# IRRemote.net
KiCad netlist of a schematic drawn in EAGLE
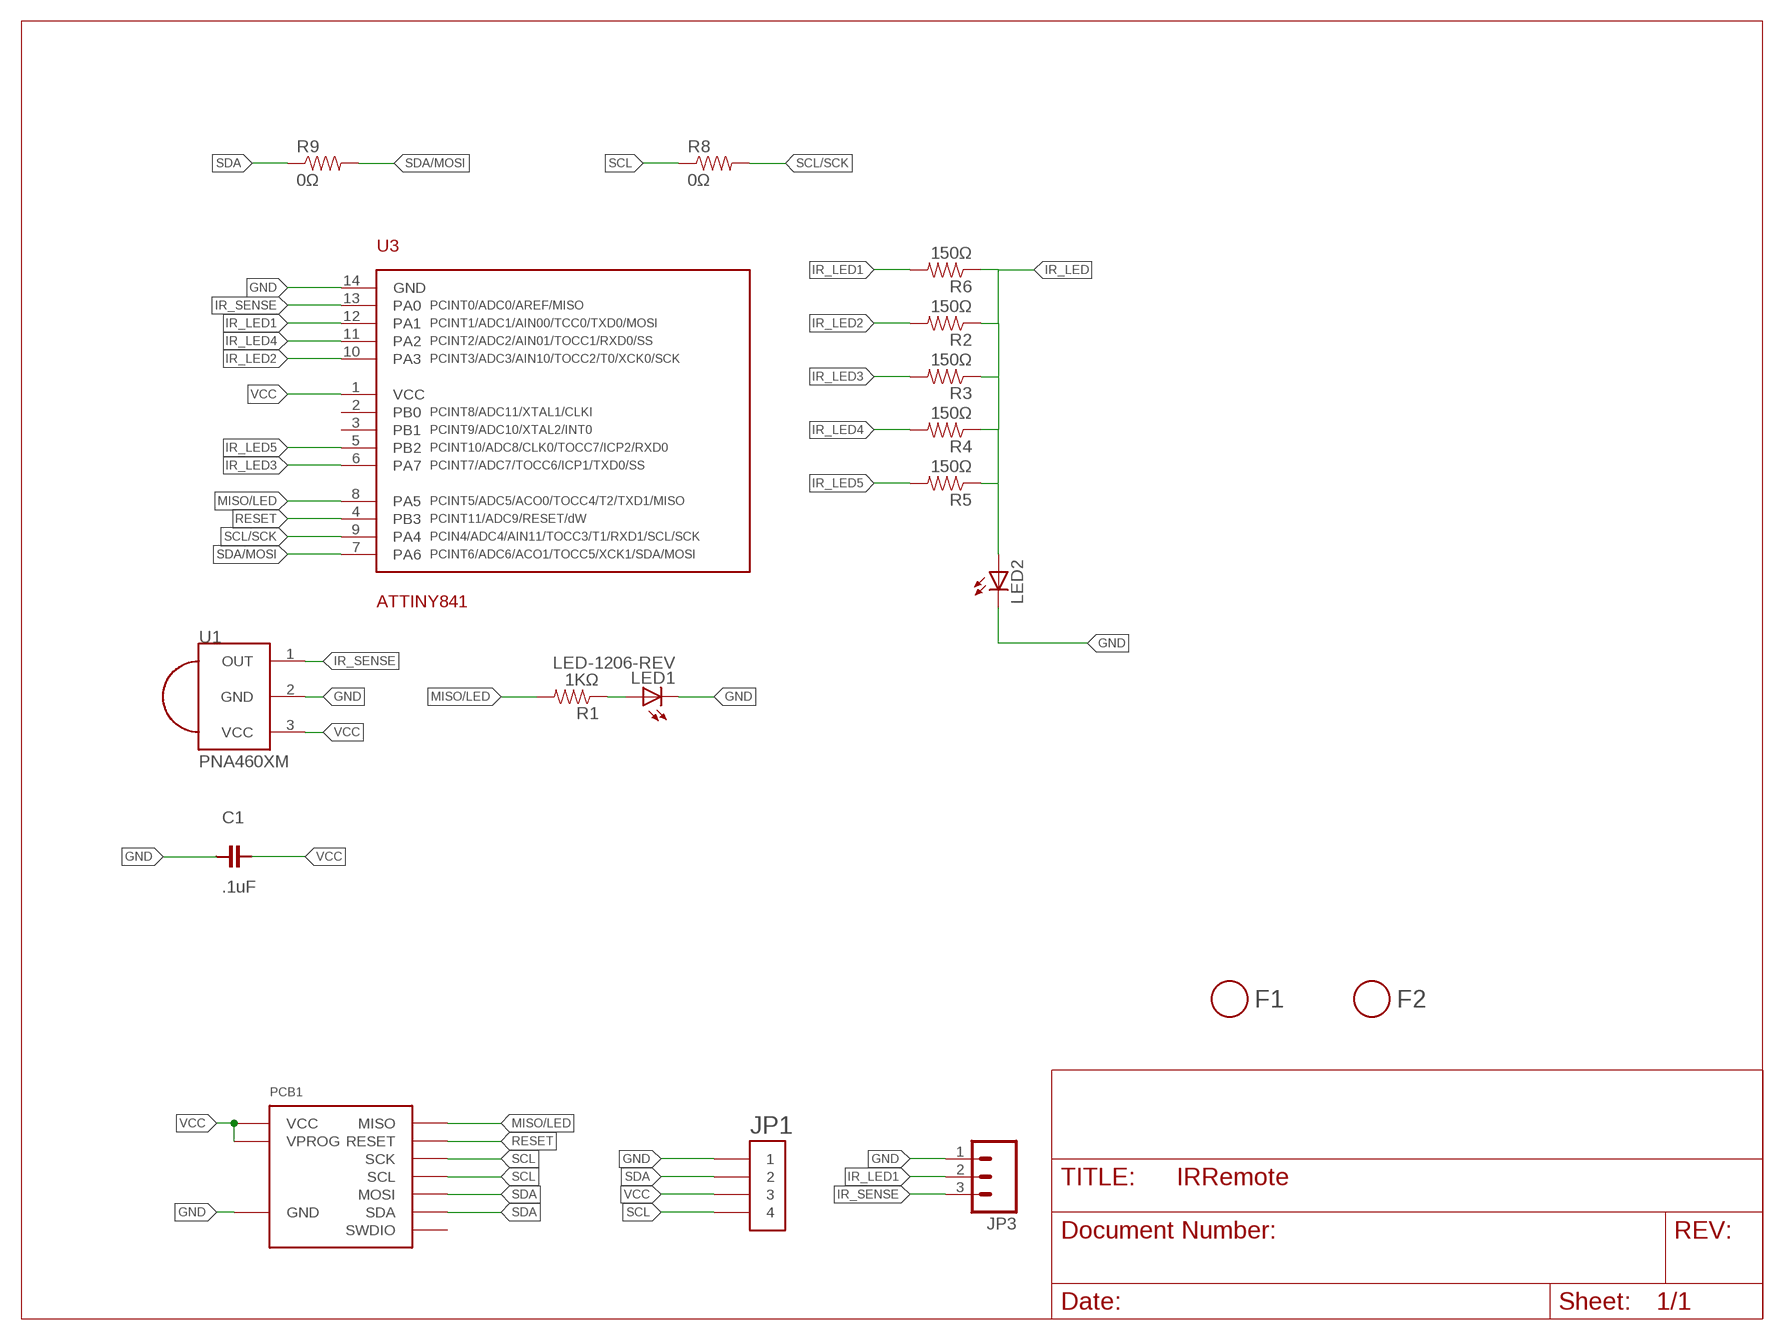
[diagram p0: schematic, sheet 1]

(export (version "E")
  (design (tool "Eeschema 10.0.6"))
  (components
    (comp (ref "C1")
      (value ".1uF")
      (footprint "eagle-import:0603")
      (fields (field (name "PARTNUM") "C0603C104K5RACTU"))
      (libsource (lib "eagle-import") (part "CAPACITOR-.1UF"))
    )
    (comp (ref "F1")
      (value "FIDUCIAL")
      (footprint "eagle-import:FIDUCIAL_1MM")
      (libsource (lib "eagle-import") (part "FIDUCIAL"))
    )
    (comp (ref "F2")
      (value "FIDUCIAL")
      (footprint "eagle-import:FIDUCIAL_1MM")
      (libsource (lib "eagle-import") (part "FIDUCIAL"))
    )
    (comp (ref "JP1")
      (value "HEADER-1X4-AMPMODU")
      (footprint "eagle-import:AMPMODU-4P")
      (fields (field (name "PARTNUM") "147721-3"))
      (libsource (lib "eagle-import") (part "HEADER-1X4-AMPMODU"))
    )
    (comp (ref "JP3")
      (value "M03PTH")
      (footprint "eagle-import:1X03")
      (libsource (lib "eagle-import") (part "M03PTH"))
    )
    (comp (ref "LED1")
      (value "LED-1206-REV")
      (footprint "eagle-import:LED-1206-REV")
      (fields (field (name "PARTNUM") "LTST-C230TBKT"))
      (libsource (lib "eagle-import") (part "LED-1206-REV"))
    )
    (comp (ref "LED2")
      (value "LED5MM")
      (footprint "eagle-import:LED5MM")
      (fields (field (name "PARTNUM") "IR928-6C-F"))
      (libsource (lib "eagle-import") (part "LED5MM"))
    )
    (comp (ref "PCB1")
      (value "DEVICE-PCB")
      (footprint "eagle-import:DEVICE-PCB")
      (fields (field (name "PARTNUM") "IRRemote PCB"))
      (libsource (lib "eagle-import") (part "DEVICE-PCB"))
    )
    (comp (ref "R1")
      (value "1KΩ")
      (footprint "eagle-import:0603")
      (fields (field (name "PARTNUM") "ERJ-3EKF1001V"))
      (libsource (lib "eagle-import") (part "RESISTOR-1KΩ"))
    )
    (comp (ref "R2")
      (value "150Ω")
      (footprint "eagle-import:0603")
      (fields (field (name "PARTNUM") "ERJ-3EKF1500V"))
      (libsource (lib "eagle-import") (part "RESISTOR-150Ω"))
    )
    (comp (ref "R3")
      (value "150Ω")
      (footprint "eagle-import:0603")
      (fields (field (name "PARTNUM") "ERJ-3EKF1500V"))
      (libsource (lib "eagle-import") (part "RESISTOR-150Ω"))
    )
    (comp (ref "R4")
      (value "150Ω")
      (footprint "eagle-import:0603")
      (fields (field (name "PARTNUM") "ERJ-3EKF1500V"))
      (libsource (lib "eagle-import") (part "RESISTOR-150Ω"))
    )
    (comp (ref "R5")
      (value "150Ω")
      (footprint "eagle-import:0603")
      (fields (field (name "PARTNUM") "ERJ-3EKF1500V"))
      (libsource (lib "eagle-import") (part "RESISTOR-150Ω"))
    )
    (comp (ref "R6")
      (value "150Ω")
      (footprint "eagle-import:0603")
      (fields (field (name "PARTNUM") "ERJ-3EKF1500V"))
      (libsource (lib "eagle-import") (part "RESISTOR-150Ω"))
    )
    (comp (ref "R8")
      (value "0Ω")
      (footprint "eagle-import:0603")
      (fields (field (name "PARTNUM") "ERJ-3GEY0R00V"))
      (libsource (lib "eagle-import") (part "RESISTOR-0Ω"))
    )
    (comp (ref "R9")
      (value "0Ω")
      (footprint "eagle-import:0603")
      (fields (field (name "PARTNUM") "ERJ-3GEY0R00V"))
      (libsource (lib "eagle-import") (part "RESISTOR-0Ω"))
    )
    (comp (ref "U1")
      (value "PNA460XM")
      (footprint "eagle-import:PNA460XM")
      (fields (field (name "PARTNUM") "TSOP38338"))
      (libsource (lib "eagle-import") (part "PNA460XM"))
    )
    (comp (ref "U3")
      (value "ATTINY841")
      (footprint "eagle-import:SOIC-14")
      (fields (field (name "PARTNUM") "ATTINY841-SSUR"))
      (libsource (lib "eagle-import") (part "ATTINY841"))
    )
  )
  (nets
    (net (code "1") (name "GND") (class "Default")
      (node (ref "C1") (pin "2") (pinfunction "2_2") (pintype "passive"))
      (node (ref "JP1") (pin "P$1") (pinfunction "1_P$1") (pintype "bidirectional"))
      (node (ref "JP1") (pin "P$2") (pinfunction "1_P$2") (pintype "bidirectional"))
      (node (ref "JP3") (pin "1") (pinfunction "1_1") (pintype "passive"))
      (node (ref "LED1") (pin "C") (pinfunction "C_C") (pintype "passive"))
      (node (ref "LED2") (pin "K") (pinfunction "C_K") (pintype "passive"))
      (node (ref "PCB1") (pin "GND") (pinfunction "GND_GND") (pintype "bidirectional"))
      (node (ref "U1") (pin "2") (pinfunction "GND_2") (pintype "power_in"))
      (node (ref "U3") (pin "14") (pinfunction "GND_14") (pintype "bidirectional"))
    )
    (net (code "2") (name "IR_LED") (class "Default")
      (node (ref "LED2") (pin "A") (pinfunction "A_A") (pintype "passive"))
      (node (ref "R2") (pin "1") (pinfunction "1_1") (pintype "passive"))
      (node (ref "R3") (pin "1") (pinfunction "1_1") (pintype "passive"))
      (node (ref "R4") (pin "1") (pinfunction "1_1") (pintype "passive"))
      (node (ref "R5") (pin "1") (pinfunction "1_1") (pintype "passive"))
      (node (ref "R6") (pin "1") (pinfunction "1_1") (pintype "passive"))
    )
    (net (code "3") (name "IR_LED1") (class "Default")
      (node (ref "JP3") (pin "2") (pinfunction "2_2") (pintype "passive"))
      (node (ref "R6") (pin "2") (pinfunction "2_2") (pintype "passive"))
      (node (ref "U3") (pin "12") (pinfunction "PA1_12") (pintype "bidirectional"))
    )
    (net (code "4") (name "IR_LED2") (class "Default")
      (node (ref "R2") (pin "2") (pinfunction "2_2") (pintype "passive"))
      (node (ref "U3") (pin "10") (pinfunction "PA3_10") (pintype "bidirectional"))
    )
    (net (code "5") (name "IR_LED3") (class "Default")
      (node (ref "R3") (pin "2") (pinfunction "2_2") (pintype "passive"))
      (node (ref "U3") (pin "6") (pinfunction "PA7_6") (pintype "bidirectional"))
    )
    (net (code "6") (name "IR_LED4") (class "Default")
      (node (ref "R4") (pin "2") (pinfunction "2_2") (pintype "passive"))
      (node (ref "U3") (pin "11") (pinfunction "PA2_11") (pintype "bidirectional"))
    )
    (net (code "7") (name "IR_LED5") (class "Default")
      (node (ref "R5") (pin "2") (pinfunction "2_2") (pintype "passive"))
      (node (ref "U3") (pin "5") (pinfunction "PB2_5") (pintype "bidirectional"))
    )
    (net (code "8") (name "IR_SENSE") (class "Default")
      (node (ref "JP3") (pin "3") (pinfunction "3_3") (pintype "passive"))
      (node (ref "U1") (pin "1") (pinfunction "OUT_1") (pintype "output"))
      (node (ref "U3") (pin "13") (pinfunction "PA0_13") (pintype "bidirectional"))
    )
    (net (code "9") (name "MISO{slash}LED") (class "Default")
      (node (ref "PCB1") (pin "MISO") (pinfunction "MISO_MISO") (pintype "bidirectional"))
      (node (ref "R1") (pin "2") (pinfunction "2_2") (pintype "passive"))
      (node (ref "U3") (pin "8") (pinfunction "PA5_8") (pintype "bidirectional"))
    )
    (net (code "10") (name "Net-(LED1-PadA)") (class "Default")
      (node (ref "LED1") (pin "A") (pinfunction "A_A") (pintype "passive"))
      (node (ref "R1") (pin "1") (pinfunction "1_1") (pintype "passive"))
    )
    (net (code "11") (name "RESET") (class "Default")
      (node (ref "PCB1") (pin "RESET") (pinfunction "RESET_RESET") (pintype "bidirectional"))
      (node (ref "U3") (pin "4") (pinfunction "PB3_4") (pintype "bidirectional"))
    )
    (net (code "12") (name "SCL") (class "Default")
      (node (ref "JP1") (pin "P$7") (pinfunction "4_P$7") (pintype "bidirectional"))
      (node (ref "JP1") (pin "P$8") (pinfunction "4_P$8") (pintype "bidirectional"))
      (node (ref "PCB1") (pin "CLK") (pinfunction "SCK_CLK") (pintype "bidirectional"))
      (node (ref "PCB1") (pin "SCL") (pinfunction "SCL_SCL") (pintype "bidirectional"))
      (node (ref "R8") (pin "1") (pinfunction "1_1") (pintype "passive"))
    )
    (net (code "13") (name "SCL{slash}SCK") (class "Default")
      (node (ref "R8") (pin "2") (pinfunction "2_2") (pintype "passive"))
      (node (ref "U3") (pin "9") (pinfunction "PA4_9") (pintype "bidirectional"))
    )
    (net (code "14") (name "SDA") (class "Default")
      (node (ref "JP1") (pin "P$3") (pinfunction "2_P$3") (pintype "bidirectional"))
      (node (ref "JP1") (pin "P$4") (pinfunction "2_P$4") (pintype "bidirectional"))
      (node (ref "PCB1") (pin "MOSI") (pinfunction "MOSI_MOSI") (pintype "bidirectional"))
      (node (ref "PCB1") (pin "SDA") (pinfunction "SDA_SDA") (pintype "bidirectional"))
      (node (ref "R9") (pin "1") (pinfunction "1_1") (pintype "passive"))
    )
    (net (code "15") (name "SDA{slash}MOSI") (class "Default")
      (node (ref "R9") (pin "2") (pinfunction "2_2") (pintype "passive"))
      (node (ref "U3") (pin "7") (pinfunction "PA6_7") (pintype "bidirectional"))
    )
    (net (code "16") (name "VCC") (class "Default")
      (node (ref "C1") (pin "1") (pinfunction "1_1") (pintype "passive"))
      (node (ref "JP1") (pin "P$5") (pinfunction "3_P$5") (pintype "bidirectional"))
      (node (ref "JP1") (pin "P$6") (pinfunction "3_P$6") (pintype "bidirectional"))
      (node (ref "PCB1") (pin "VCC") (pinfunction "VCC_VCC") (pintype "bidirectional"))
      (node (ref "PCB1") (pin "VPROG") (pinfunction "VPROG_VPROG") (pintype "bidirectional"))
      (node (ref "U1") (pin "3") (pinfunction "VCC_3") (pintype "power_in"))
      (node (ref "U3") (pin "1") (pinfunction "VCC_1") (pintype "bidirectional"))
    )
    (net (code "17") (name "unconnected-(PCB1-PadSWDIO)") (class "Default")
      (node (ref "PCB1") (pin "SWDIO") (pinfunction "SWDIO_SWDIO") (pintype "bidirectional"))
    )
    (net (code "18") (name "unconnected-(U3-PB0-Pad2)") (class "Default")
      (node (ref "U3") (pin "2") (pinfunction "PB0_2") (pintype "bidirectional"))
    )
    (net (code "19") (name "unconnected-(U3-PB1-Pad3)") (class "Default")
      (node (ref "U3") (pin "3") (pinfunction "PB1_3") (pintype "bidirectional"))
    )
  )
)
